# ESP32.net
KiCad netlist of a schematic drawn in EAGLE
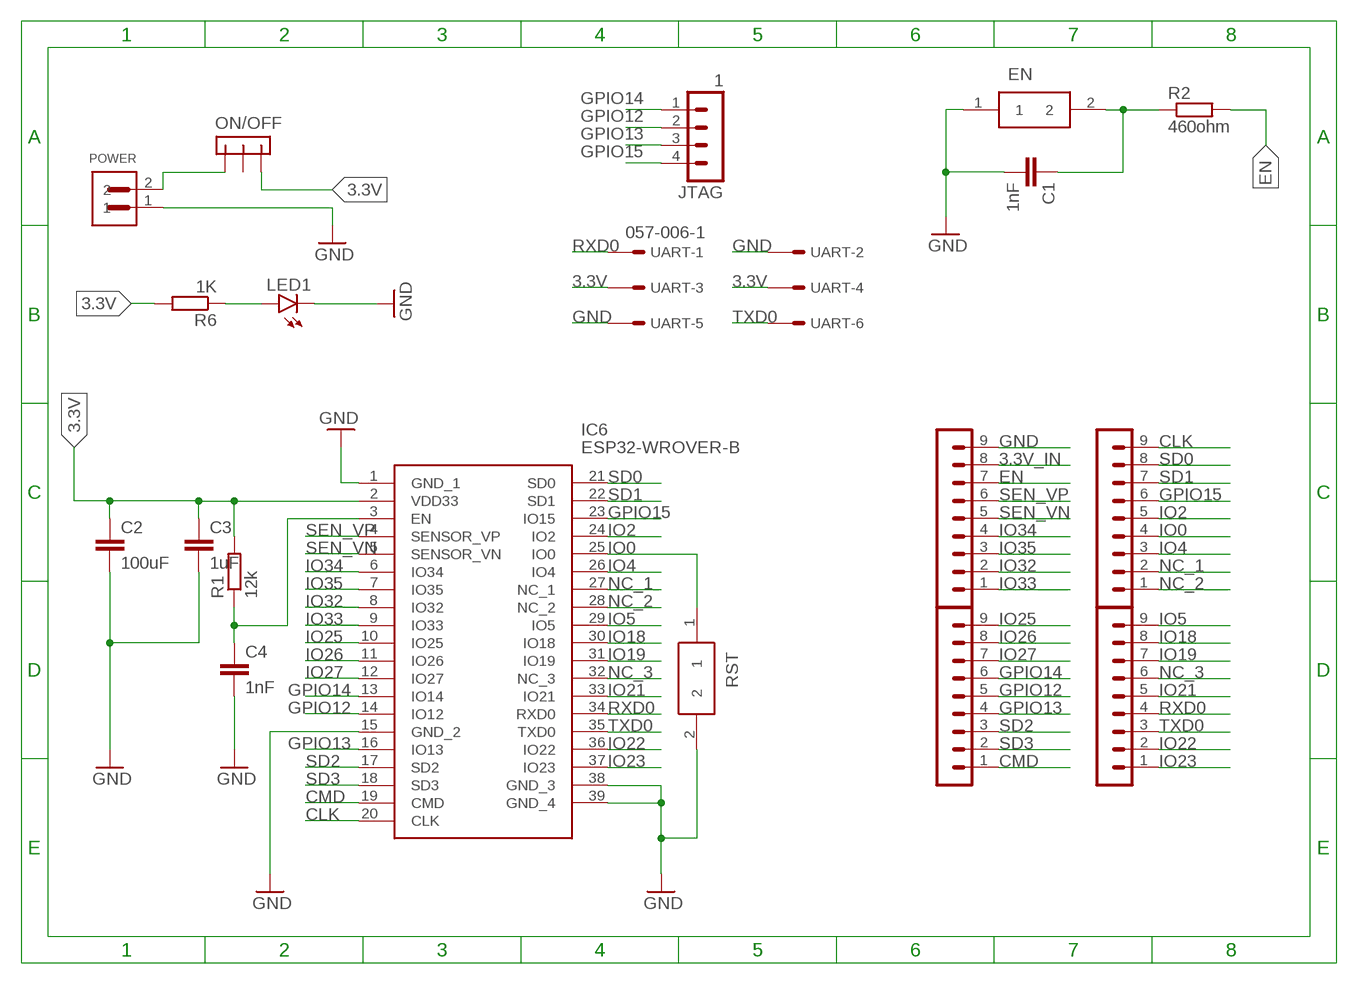
[diagram p0: schematic, sheet 1]

(export (version "E")
  (design (tool "Eeschema 10.0.6"))
  (components
    (comp (ref "C1")
      (value "1nF")
      (footprint "eagle-import:C0805")
      (libsource (lib "eagle-import") (part "C-EU_805C0805"))
    )
    (comp (ref "C2")
      (value "100uF")
      (footprint "eagle-import:C1206")
      (libsource (lib "eagle-import") (part "C-EU_1206C1206"))
    )
    (comp (ref "C3")
      (value "1uF")
      (footprint "eagle-import:C0805")
      (libsource (lib "eagle-import") (part "C-EU_805C0805"))
    )
    (comp (ref "C4")
      (value "1nF")
      (footprint "eagle-import:C0805")
      (libsource (lib "eagle-import") (part "C-EU_805C0805"))
    )
    (comp (ref "EN")
      (value "FSMSMTR")
      (footprint "eagle-import:FSMSM")
      (fields (field (name "MOUSER_PART_NUMBER") "506-FSMSMTR") (field (name "RS_PART_NUMBER") "1680547"))
      (libsource (lib "eagle-import") (part "FSMSMTR"))
    )
    (comp (ref "IC6")
      (value "ESP32-WROVER-B")
      (footprint "eagle-import:ESP32WROVERIB16MB")
      (fields (field (name "MOUSER_PART_NUMBER") "356-ESP32-WROVER-B"))
      (libsource (lib "eagle-import") (part "ESP32-WROVER-B"))
    )
    (comp (ref "JTAG")
      (value "1")
      (footprint "eagle-import:MA04-1")
      (libsource (lib "eagle-import") (part "MA04-1"))
    )
    (comp (ref "LED1")
      (value "LEDSMT1206")
      (footprint "eagle-import:1206")
      (libsource (lib "eagle-import") (part "LEDSMT1206"))
    )
    (comp (ref "ON/OFF")
      (value "-CON3")
      (footprint "eagle-import:CON3")
      (libsource (lib "eagle-import") (part "-CON3"))
    )
    (comp (ref "POWER")
      (value "S2B-PH-SM4-TB")
      (footprint "eagle-import:JST_S2B-PH-SM4-TB")
      (fields (field (name "MF") "JST Sales"))
      (libsource (lib "eagle-import") (part "S2B-PH-SM4-TB"))
    )
    (comp (ref "R1")
      (value "12k")
      (footprint "eagle-import:R0805")
      (libsource (lib "eagle-import") (part "R-EU_805R0805"))
    )
    (comp (ref "R2")
      (value "460ohm")
      (footprint "eagle-import:R0805")
      (libsource (lib "eagle-import") (part "R-EU_805R0805"))
    )
    (comp (ref "R6")
      (value "1K")
      (footprint "eagle-import:R1206")
      (libsource (lib "eagle-import") (part "R-EU_R1206"))
    )
    (comp (ref "RST")
      (value "FSMSMTR")
      (footprint "eagle-import:FSMSM")
      (fields (field (name "MOUSER_PART_NUMBER") "506-FSMSMTR") (field (name "RS_PART_NUMBER") "1680547"))
      (libsource (lib "eagle-import") (part "FSMSMTR"))
    )
    (comp (ref "SV1")
      (value "PINHEADER-1X9")
      (footprint "eagle-import:MA09-1")
      (libsource (lib "eagle-import") (part "PINHEADER-1X9"))
    )
    (comp (ref "SV2")
      (value "PINHEADER-1X9")
      (footprint "eagle-import:MA09-1")
      (libsource (lib "eagle-import") (part "PINHEADER-1X9"))
    )
    (comp (ref "SV5")
      (value "PINHEADER-1X9")
      (footprint "eagle-import:MA09-1")
      (libsource (lib "eagle-import") (part "PINHEADER-1X9"))
    )
    (comp (ref "SV6")
      (value "PINHEADER-1X9")
      (footprint "eagle-import:MA09-1")
      (libsource (lib "eagle-import") (part "PINHEADER-1X9"))
    )
    (comp (ref "UART")
      (value "057-006-1")
      (footprint "eagle-import:057-006-1")
      (libsource (lib "eagle-import") (part "057-006-1"))
    )
  )
  (nets
    (net (code "1") (name "3.3V") (class "Default")
      (node (ref "C2") (pin "1") (pinfunction "1_1") (pintype "passive"))
      (node (ref "C3") (pin "1") (pinfunction "1_1") (pintype "passive"))
      (node (ref "IC6") (pin "2") (pinfunction "VDD33_2") (pintype "bidirectional"))
      (node (ref "ON/OFF") (pin "P$1") (pinfunction "1_P$1") (pintype "passive"))
      (node (ref "R1") (pin "2") (pinfunction "2_2") (pintype "passive"))
      (node (ref "R6") (pin "2") (pinfunction "2_2") (pintype "passive"))
      (node (ref "UART") (pin "3") (pinfunction "S_3") (pintype "passive"))
      (node (ref "UART") (pin "4") (pinfunction "S_4") (pintype "passive"))
    )
    (net (code "2") (name "3.3V_IN") (class "Default")
      (node (ref "ON/OFF") (pin "P$3") (pinfunction "3_P$3") (pintype "passive"))
      (node (ref "POWER") (pin "2") (pinfunction "2_2") (pintype "passive"))
      (node (ref "SV5") (pin "8") (pinfunction "8_8") (pintype "passive"))
    )
    (net (code "3") (name "CLK") (class "Default")
      (node (ref "IC6") (pin "20") (pinfunction "CLK_20") (pintype "bidirectional"))
      (node (ref "SV1") (pin "9") (pinfunction "9_9") (pintype "passive"))
    )
    (net (code "4") (name "CMD") (class "Default")
      (node (ref "IC6") (pin "19") (pinfunction "CMD_19") (pintype "bidirectional"))
      (node (ref "SV6") (pin "1") (pinfunction "1_1") (pintype "passive"))
    )
    (net (code "5") (name "EN") (class "Default")
      (node (ref "C1") (pin "1") (pinfunction "1_1") (pintype "passive"))
      (node (ref "C4") (pin "1") (pinfunction "1_1") (pintype "passive"))
      (node (ref "EN") (pin "2") (pinfunction "2_2") (pintype "bidirectional"))
      (node (ref "IC6") (pin "3") (pinfunction "EN_3") (pintype "bidirectional"))
      (node (ref "R1") (pin "1") (pinfunction "1_1") (pintype "passive"))
      (node (ref "R2") (pin "1") (pinfunction "1_1") (pintype "passive"))
      (node (ref "R2") (pin "2") (pinfunction "2_2") (pintype "passive"))
      (node (ref "SV5") (pin "7") (pinfunction "7_7") (pintype "passive"))
    )
    (net (code "6") (name "GND") (class "Default")
      (node (ref "C1") (pin "2") (pinfunction "2_2") (pintype "passive"))
      (node (ref "C2") (pin "2") (pinfunction "2_2") (pintype "passive"))
      (node (ref "C3") (pin "2") (pinfunction "2_2") (pintype "passive"))
      (node (ref "C4") (pin "2") (pinfunction "2_2") (pintype "passive"))
      (node (ref "EN") (pin "1") (pinfunction "1_1") (pintype "bidirectional"))
      (node (ref "IC6") (pin "1") (pinfunction "GND_1_1") (pintype "bidirectional"))
      (node (ref "IC6") (pin "15") (pinfunction "GND_2_15") (pintype "bidirectional"))
      (node (ref "IC6") (pin "38") (pinfunction "GND_3_38") (pintype "bidirectional"))
      (node (ref "IC6") (pin "39") (pinfunction "GND_4_39") (pintype "bidirectional"))
      (node (ref "LED1") (pin "C") (pinfunction "C_C") (pintype "passive"))
      (node (ref "POWER") (pin "1") (pinfunction "1_1") (pintype "passive"))
      (node (ref "RST") (pin "2") (pinfunction "2_2") (pintype "bidirectional"))
      (node (ref "SV5") (pin "9") (pinfunction "9_9") (pintype "passive"))
      (node (ref "UART") (pin "2") (pinfunction "S_2") (pintype "passive"))
      (node (ref "UART") (pin "5") (pinfunction "S_5") (pintype "passive"))
    )
    (net (code "7") (name "GPIO12") (class "Default")
      (node (ref "IC6") (pin "14") (pinfunction "IO12_14") (pintype "bidirectional"))
      (node (ref "JTAG") (pin "2") (pinfunction "2_2") (pintype "passive"))
      (node (ref "SV6") (pin "5") (pinfunction "5_5") (pintype "passive"))
    )
    (net (code "8") (name "GPIO13") (class "Default")
      (node (ref "IC6") (pin "16") (pinfunction "IO13_16") (pintype "bidirectional"))
      (node (ref "JTAG") (pin "3") (pinfunction "3_3") (pintype "passive"))
      (node (ref "SV6") (pin "4") (pinfunction "4_4") (pintype "passive"))
    )
    (net (code "9") (name "GPIO14") (class "Default")
      (node (ref "IC6") (pin "13") (pinfunction "IO14_13") (pintype "bidirectional"))
      (node (ref "JTAG") (pin "1") (pinfunction "1_1") (pintype "passive"))
      (node (ref "SV6") (pin "6") (pinfunction "6_6") (pintype "passive"))
    )
    (net (code "10") (name "GPIO15") (class "Default")
      (node (ref "IC6") (pin "23") (pinfunction "IO15_23") (pintype "bidirectional"))
      (node (ref "JTAG") (pin "4") (pinfunction "4_4") (pintype "passive"))
      (node (ref "SV1") (pin "6") (pinfunction "6_6") (pintype "passive"))
    )
    (net (code "11") (name "IO0") (class "Default")
      (node (ref "IC6") (pin "25") (pinfunction "IO0_25") (pintype "bidirectional"))
      (node (ref "RST") (pin "1") (pinfunction "1_1") (pintype "bidirectional"))
      (node (ref "SV1") (pin "4") (pinfunction "4_4") (pintype "passive"))
    )
    (net (code "12") (name "IO2") (class "Default")
      (node (ref "IC6") (pin "24") (pinfunction "IO2_24") (pintype "bidirectional"))
      (node (ref "SV1") (pin "5") (pinfunction "5_5") (pintype "passive"))
    )
    (net (code "13") (name "IO4") (class "Default")
      (node (ref "IC6") (pin "26") (pinfunction "IO4_26") (pintype "bidirectional"))
      (node (ref "SV1") (pin "3") (pinfunction "3_3") (pintype "passive"))
    )
    (net (code "14") (name "IO5") (class "Default")
      (node (ref "IC6") (pin "29") (pinfunction "IO5_29") (pintype "bidirectional"))
      (node (ref "SV2") (pin "9") (pinfunction "9_9") (pintype "passive"))
    )
    (net (code "15") (name "IO18") (class "Default")
      (node (ref "IC6") (pin "30") (pinfunction "IO18_30") (pintype "bidirectional"))
      (node (ref "SV2") (pin "8") (pinfunction "8_8") (pintype "passive"))
    )
    (net (code "16") (name "IO19") (class "Default")
      (node (ref "IC6") (pin "31") (pinfunction "IO19_31") (pintype "bidirectional"))
      (node (ref "SV2") (pin "7") (pinfunction "7_7") (pintype "passive"))
    )
    (net (code "17") (name "IO21") (class "Default")
      (node (ref "IC6") (pin "33") (pinfunction "IO21_33") (pintype "bidirectional"))
      (node (ref "SV2") (pin "5") (pinfunction "5_5") (pintype "passive"))
    )
    (net (code "18") (name "IO22") (class "Default")
      (node (ref "IC6") (pin "36") (pinfunction "IO22_36") (pintype "bidirectional"))
      (node (ref "SV2") (pin "2") (pinfunction "2_2") (pintype "passive"))
    )
    (net (code "19") (name "IO23") (class "Default")
      (node (ref "IC6") (pin "37") (pinfunction "IO23_37") (pintype "bidirectional"))
      (node (ref "SV2") (pin "1") (pinfunction "1_1") (pintype "passive"))
    )
    (net (code "20") (name "IO25") (class "Default")
      (node (ref "IC6") (pin "10") (pinfunction "IO25_10") (pintype "bidirectional"))
      (node (ref "SV6") (pin "9") (pinfunction "9_9") (pintype "passive"))
    )
    (net (code "21") (name "IO26") (class "Default")
      (node (ref "IC6") (pin "11") (pinfunction "IO26_11") (pintype "bidirectional"))
      (node (ref "SV6") (pin "8") (pinfunction "8_8") (pintype "passive"))
    )
    (net (code "22") (name "IO27") (class "Default")
      (node (ref "IC6") (pin "12") (pinfunction "IO27_12") (pintype "bidirectional"))
      (node (ref "SV6") (pin "7") (pinfunction "7_7") (pintype "passive"))
    )
    (net (code "23") (name "IO32") (class "Default")
      (node (ref "IC6") (pin "8") (pinfunction "IO32_8") (pintype "bidirectional"))
      (node (ref "SV5") (pin "2") (pinfunction "2_2") (pintype "passive"))
    )
    (net (code "24") (name "IO33") (class "Default")
      (node (ref "IC6") (pin "9") (pinfunction "IO33_9") (pintype "bidirectional"))
      (node (ref "SV5") (pin "1") (pinfunction "1_1") (pintype "passive"))
    )
    (net (code "25") (name "IO34") (class "Default")
      (node (ref "IC6") (pin "6") (pinfunction "IO34_6") (pintype "bidirectional"))
      (node (ref "SV5") (pin "4") (pinfunction "4_4") (pintype "passive"))
    )
    (net (code "26") (name "IO35") (class "Default")
      (node (ref "IC6") (pin "7") (pinfunction "IO35_7") (pintype "bidirectional"))
      (node (ref "SV5") (pin "3") (pinfunction "3_3") (pintype "passive"))
    )
    (net (code "27") (name "NC_1") (class "Default")
      (node (ref "IC6") (pin "27") (pinfunction "NC_1_27") (pintype "bidirectional"))
      (node (ref "SV1") (pin "2") (pinfunction "2_2") (pintype "passive"))
    )
    (net (code "28") (name "NC_2") (class "Default")
      (node (ref "IC6") (pin "28") (pinfunction "NC_2_28") (pintype "bidirectional"))
      (node (ref "SV1") (pin "1") (pinfunction "1_1") (pintype "passive"))
    )
    (net (code "29") (name "NC_3") (class "Default")
      (node (ref "IC6") (pin "32") (pinfunction "NC_3_32") (pintype "bidirectional"))
      (node (ref "SV2") (pin "6") (pinfunction "6_6") (pintype "passive"))
    )
    (net (code "30") (name "Net-(LED1-PadA)") (class "Default")
      (node (ref "LED1") (pin "A") (pinfunction "A_A") (pintype "passive"))
      (node (ref "R6") (pin "1") (pinfunction "1_1") (pintype "passive"))
    )
    (net (code "31") (name "RXD0") (class "Default")
      (node (ref "IC6") (pin "34") (pinfunction "RXD0_34") (pintype "bidirectional"))
      (node (ref "SV2") (pin "4") (pinfunction "4_4") (pintype "passive"))
      (node (ref "UART") (pin "1") (pinfunction "S_1") (pintype "passive"))
    )
    (net (code "32") (name "SD0") (class "Default")
      (node (ref "IC6") (pin "21") (pinfunction "SD0_21") (pintype "bidirectional"))
      (node (ref "SV1") (pin "8") (pinfunction "8_8") (pintype "passive"))
    )
    (net (code "33") (name "SD1") (class "Default")
      (node (ref "IC6") (pin "22") (pinfunction "SD1_22") (pintype "bidirectional"))
      (node (ref "SV1") (pin "7") (pinfunction "7_7") (pintype "passive"))
    )
    (net (code "34") (name "SD2") (class "Default")
      (node (ref "IC6") (pin "17") (pinfunction "SD2_17") (pintype "bidirectional"))
      (node (ref "SV6") (pin "3") (pinfunction "3_3") (pintype "passive"))
    )
    (net (code "35") (name "SD3") (class "Default")
      (node (ref "IC6") (pin "18") (pinfunction "SD3_18") (pintype "bidirectional"))
      (node (ref "SV6") (pin "2") (pinfunction "2_2") (pintype "passive"))
    )
    (net (code "36") (name "SEN_VN") (class "Default")
      (node (ref "IC6") (pin "5") (pinfunction "SENSOR_VN_5") (pintype "bidirectional"))
      (node (ref "SV5") (pin "5") (pinfunction "5_5") (pintype "passive"))
    )
    (net (code "37") (name "SEN_VP") (class "Default")
      (node (ref "IC6") (pin "4") (pinfunction "SENSOR_VP_4") (pintype "bidirectional"))
      (node (ref "SV5") (pin "6") (pinfunction "6_6") (pintype "passive"))
    )
    (net (code "38") (name "TXD0") (class "Default")
      (node (ref "IC6") (pin "35") (pinfunction "TXD0_35") (pintype "bidirectional"))
      (node (ref "SV2") (pin "3") (pinfunction "3_3") (pintype "passive"))
      (node (ref "UART") (pin "6") (pinfunction "S_6") (pintype "passive"))
    )
    (net (code "39") (name "unconnected-(ON/OFF-2-PadP$2)") (class "Default")
      (node (ref "ON/OFF") (pin "P$2") (pinfunction "2_P$2") (pintype "passive"))
    )
  )
)
